# Schematic.net
KiCad netlist of a schematic drawn in EAGLE
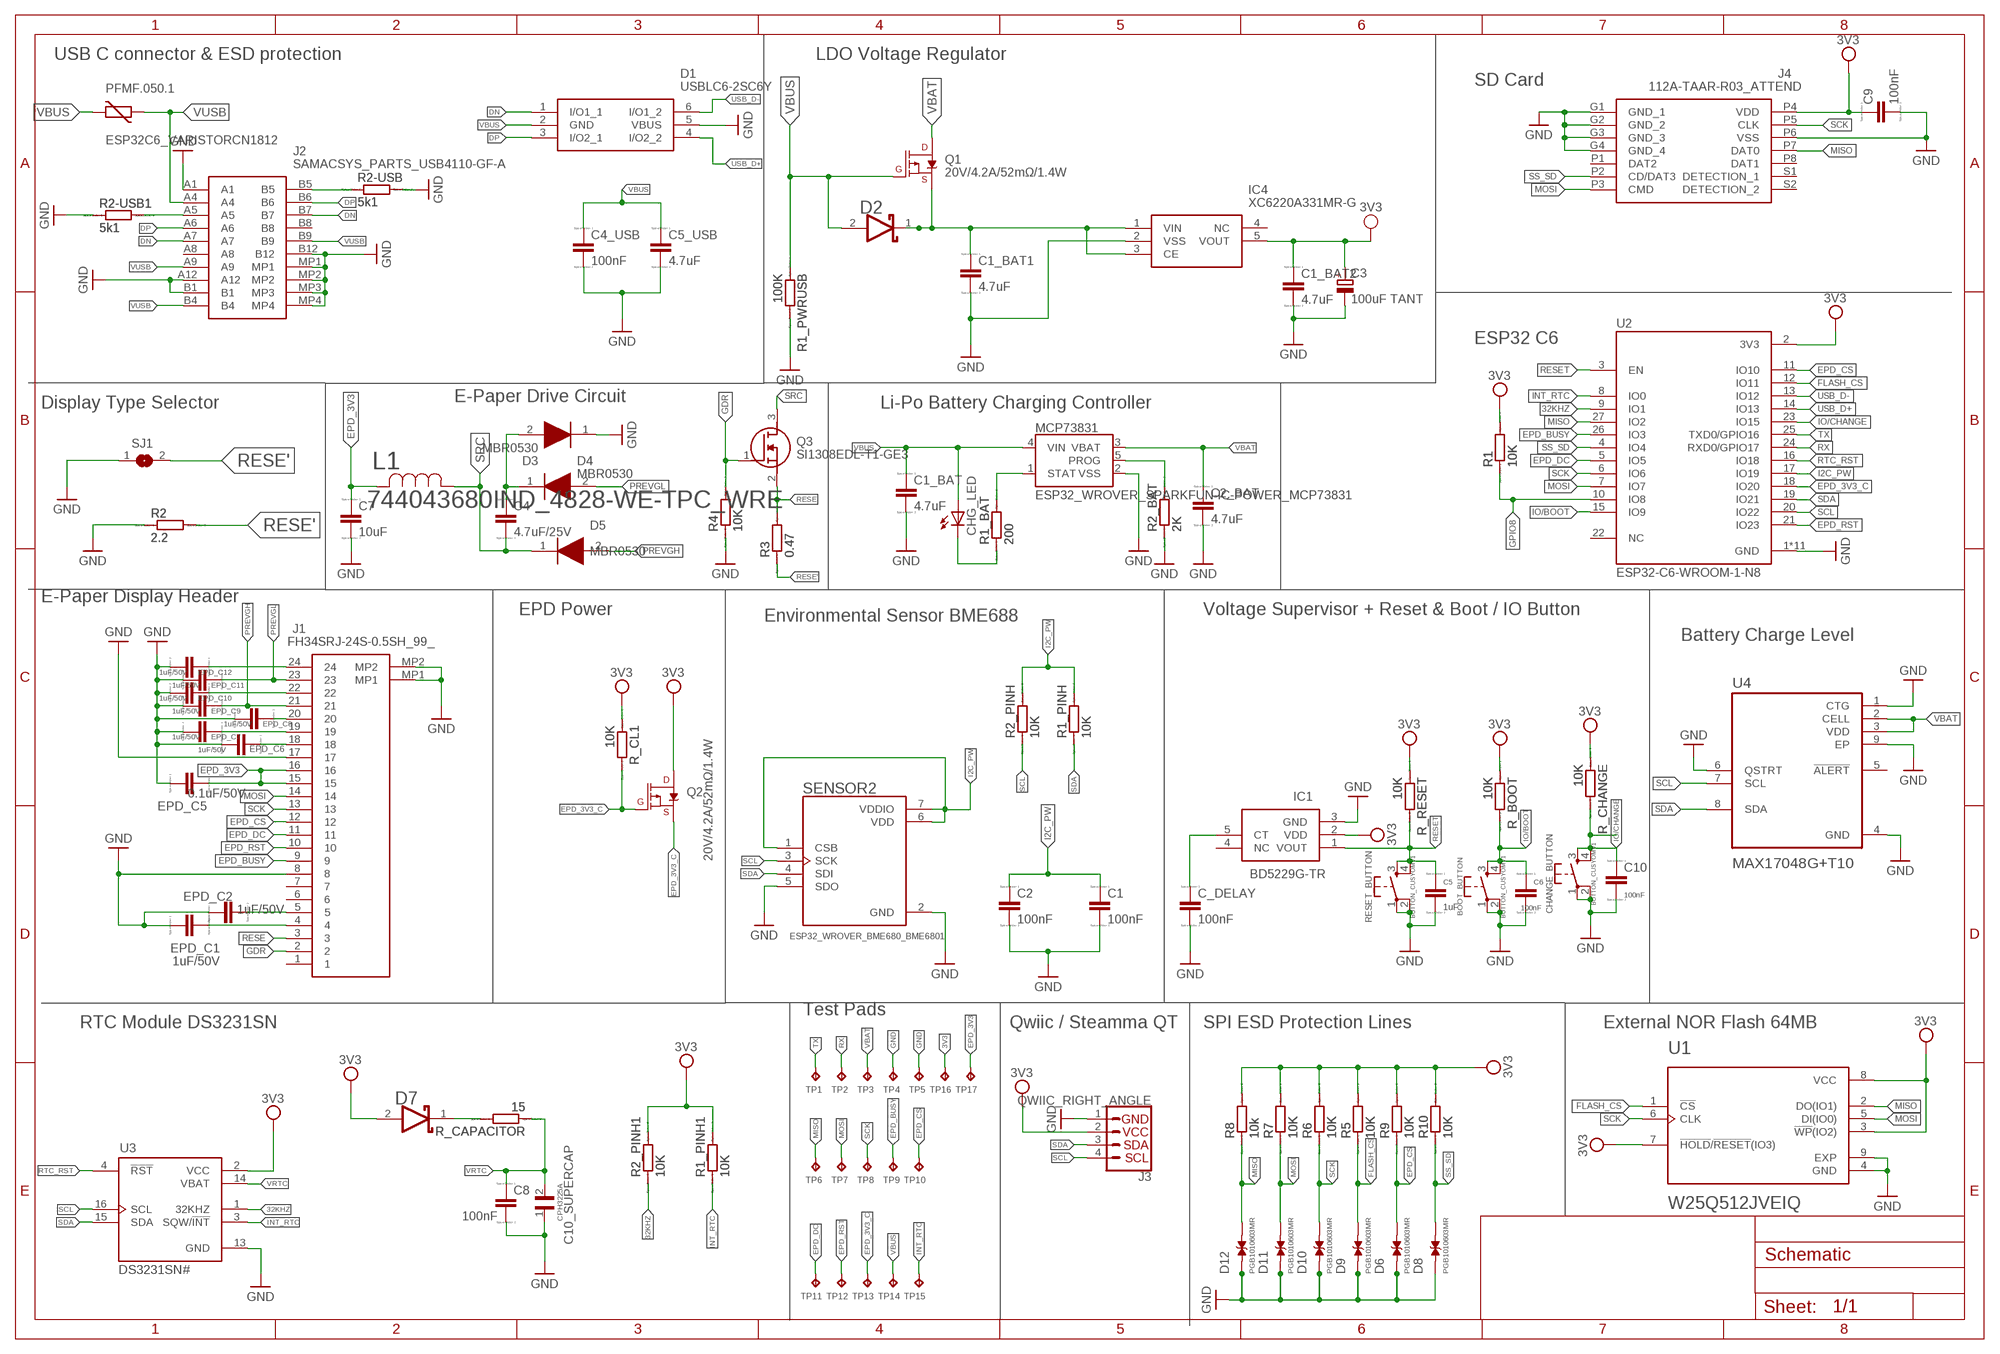
[diagram p0: schematic, sheet 1]

(export (version "E")
  (design (tool "Eeschema 10.0.6"))
  (components
    (comp (ref "BOOT_BUTTON")
      (value "BUTTON_CUSYOMV1")
      (footprint "eagle-import:MYBUTTON")
      (libsource (lib "eagle-import") (part "BUTTON_CUSYOMV1"))
    )
    (comp (ref "C1")
      (value "100nF")
      (footprint "eagle-import:ESP32_WROVER_EAGLE-LTSPICE_C0402")
      (libsource (lib "eagle-import") (part "ESP32_WROVER_EAGLE-LTSPICE_CC0402"))
    )
    (comp (ref "C1_BAT")
      (value "4.7uF")
      (footprint "eagle-import:ESP32_WROVER_EAGLE-LTSPICE_C0402")
      (libsource (lib "eagle-import") (part "ESP32_WROVER_EAGLE-LTSPICE_CC0402"))
    )
    (comp (ref "C1_BAT1")
      (value "4.7uF")
      (footprint "eagle-import:ESP32_WROVER_EAGLE-LTSPICE_C0402")
      (libsource (lib "eagle-import") (part "ESP32_WROVER_EAGLE-LTSPICE_CC0402"))
    )
    (comp (ref "C1_BAT2")
      (value "4.7uF")
      (footprint "eagle-import:ESP32_WROVER_EAGLE-LTSPICE_C0402")
      (libsource (lib "eagle-import") (part "ESP32_WROVER_EAGLE-LTSPICE_CC0402"))
    )
    (comp (ref "C2")
      (value "100nF")
      (footprint "eagle-import:ESP32_WROVER_EAGLE-LTSPICE_C0402")
      (libsource (lib "eagle-import") (part "ESP32_WROVER_EAGLE-LTSPICE_CC0402"))
    )
    (comp (ref "C2_BAT")
      (value "4.7uF")
      (footprint "eagle-import:ESP32_WROVER_EAGLE-LTSPICE_C0402")
      (libsource (lib "eagle-import") (part "ESP32_WROVER_EAGLE-LTSPICE_CC0402"))
    )
    (comp (ref "C3")
      (value "100uF TANT")
      (footprint "eagle-import:RCL_CT3528")
      (libsource (lib "eagle-import") (part "RCL_CPOL-EUCT3528"))
    )
    (comp (ref "C4")
      (value "4.7uF/25V")
      (footprint "eagle-import:ESP32_WROVER_EAGLE-LTSPICE_C0402")
      (libsource (lib "eagle-import") (part "ESP32_WROVER_EAGLE-LTSPICE_CC0402"))
    )
    (comp (ref "C4_USB")
      (value "100nF")
      (footprint "eagle-import:ESP32_WROVER_EAGLE-LTSPICE_C0402")
      (libsource (lib "eagle-import") (part "ESP32_WROVER_EAGLE-LTSPICE_CC0402"))
    )
    (comp (ref "C5")
      (value "1uF")
      (footprint "eagle-import:ESP32_WROVER_EAGLE-LTSPICE_C0402")
      (libsource (lib "eagle-import") (part "ESP32_WROVER_EAGLE-LTSPICE_CC0402"))
    )
    (comp (ref "C5_USB")
      (value "4.7uF")
      (footprint "eagle-import:ESP32_WROVER_EAGLE-LTSPICE_C0402")
      (libsource (lib "eagle-import") (part "ESP32_WROVER_EAGLE-LTSPICE_CC0402"))
    )
    (comp (ref "C6")
      (value "100nF")
      (footprint "eagle-import:ESP32_WROVER_EAGLE-LTSPICE_C0402")
      (libsource (lib "eagle-import") (part "ESP32_WROVER_EAGLE-LTSPICE_CC0402"))
    )
    (comp (ref "C7")
      (value "10uF")
      (footprint "eagle-import:ESP32_WROVER_EAGLE-LTSPICE_C0402")
      (libsource (lib "eagle-import") (part "ESP32_WROVER_EAGLE-LTSPICE_CC0402"))
    )
    (comp (ref "C8")
      (value "100nF")
      (footprint "eagle-import:ESP32_WROVER_EAGLE-LTSPICE_C0402")
      (libsource (lib "eagle-import") (part "ESP32_WROVER_EAGLE-LTSPICE_CC0402"))
    )
    (comp (ref "C9")
      (value "100nF")
      (footprint "eagle-import:ESP32_WROVER_EAGLE-LTSPICE_C0402")
      (libsource (lib "eagle-import") (part "ESP32_WROVER_EAGLE-LTSPICE_CC0402"))
    )
    (comp (ref "C10")
      (value "100nF")
      (footprint "eagle-import:ESP32_WROVER_EAGLE-LTSPICE_C0402")
      (libsource (lib "eagle-import") (part "ESP32_WROVER_EAGLE-LTSPICE_CC0402"))
    )
    (comp (ref "C10_SUPERCAP")
      (value "CPH3225A")
      (footprint "eagle-import:CAPCP3225X100N")
      (fields (field (name "MF") "Seiko Instruments"))
      (libsource (lib "eagle-import") (part "CPH3225A"))
    )
    (comp (ref "CHANGE_BUTTON")
      (value "BUTTON_CUSYOMV1")
      (footprint "eagle-import:MYBUTTON")
      (libsource (lib "eagle-import") (part "BUTTON_CUSYOMV1"))
    )
    (comp (ref "CHG_LED")
      (value "ADAFRUIT_LEDCHIP-LED0603")
      (footprint "eagle-import:ADAFRUIT_CHIP-LED0603")
      (libsource (lib "eagle-import") (part "ADAFRUIT_LEDCHIP-LED0603"))
    )
    (comp (ref "C_DELAY")
      (value "100nF")
      (footprint "eagle-import:ESP32_WROVER_EAGLE-LTSPICE_C0402")
      (libsource (lib "eagle-import") (part "ESP32_WROVER_EAGLE-LTSPICE_CC0402"))
    )
    (comp (ref "D1")
      (value "USBLC6-2SC6Y")
      (footprint "eagle-import:SOT95P280X145-6N")
      (fields (field (name "MF") "STMicroelectronics"))
      (libsource (lib "eagle-import") (part "USBLC6-2SC6Y"))
    )
    (comp (ref "D2")
      (value "ESP32_WROVER_AVX---SD0805S020S1R0_AVX_SD0805S020S1R0_0_0AVX_SD0805S020S1R0_0_0")
      (footprint "eagle-import:ESP32_WROVER_AVX---SD0805S020S1R0_AVX_SD0805S020S1R0_0")
      (fields
        (field (name "DIGIKEY_PART_NUMBER") "478-7800-1-ND")
        (field (name "MF") "AVX")
        (field (name "MOUSER_PART_NUMBER") "581-SD0805S020S1R0")
      )
      (libsource (lib "eagle-import") (part "ESP32_WROVER_AVX---SD0805S020S1R0_AVX_SD0805S020S1R0_0_0AVX_SD0805S020S1R0_0_0"))
    )
    (comp (ref "D3")
      (value "MBR0530")
      (footprint "eagle-import:SOD3716X135N")
      (fields (field (name "MF") "ON Semiconductor"))
      (libsource (lib "eagle-import") (part "MBR0530"))
    )
    (comp (ref "D4")
      (value "MBR0530")
      (footprint "eagle-import:SOD3716X135N")
      (fields (field (name "MF") "ON Semiconductor"))
      (libsource (lib "eagle-import") (part "MBR0530"))
    )
    (comp (ref "D5")
      (value "MBR0530")
      (footprint "eagle-import:SOD3716X135N")
      (fields (field (name "MF") "ON Semiconductor"))
      (libsource (lib "eagle-import") (part "MBR0530"))
    )
    (comp (ref "D6")
      (value "PGB1010603MR")
      (footprint "eagle-import:DIOC1608X36N")
      (fields (field (name "MF") "Littelfuse Inc."))
      (libsource (lib "eagle-import") (part "PGB1010603MR"))
    )
    (comp (ref "D7")
      (value "ESP32_WROVER_AVX---SD0805S020S1R0_AVX_SD0805S020S1R0_0_0AVX_SD0805S020S1R0_0_0")
      (footprint "eagle-import:ESP32_WROVER_AVX---SD0805S020S1R0_AVX_SD0805S020S1R0_0")
      (fields
        (field (name "DIGIKEY_PART_NUMBER") "478-7800-1-ND")
        (field (name "MF") "AVX")
        (field (name "MOUSER_PART_NUMBER") "581-SD0805S020S1R0")
      )
      (libsource (lib "eagle-import") (part "ESP32_WROVER_AVX---SD0805S020S1R0_AVX_SD0805S020S1R0_0_0AVX_SD0805S020S1R0_0_0"))
    )
    (comp (ref "D8")
      (value "PGB1010603MR")
      (footprint "eagle-import:DIOC1608X36N")
      (fields (field (name "MF") "Littelfuse Inc."))
      (libsource (lib "eagle-import") (part "PGB1010603MR"))
    )
    (comp (ref "D9")
      (value "PGB1010603MR")
      (footprint "eagle-import:DIOC1608X36N")
      (fields (field (name "MF") "Littelfuse Inc."))
      (libsource (lib "eagle-import") (part "PGB1010603MR"))
    )
    (comp (ref "D10")
      (value "PGB1010603MR")
      (footprint "eagle-import:DIOC1608X36N")
      (fields (field (name "MF") "Littelfuse Inc."))
      (libsource (lib "eagle-import") (part "PGB1010603MR"))
    )
    (comp (ref "D11")
      (value "PGB1010603MR")
      (footprint "eagle-import:DIOC1608X36N")
      (fields (field (name "MF") "Littelfuse Inc."))
      (libsource (lib "eagle-import") (part "PGB1010603MR"))
    )
    (comp (ref "D12")
      (value "PGB1010603MR")
      (footprint "eagle-import:DIOC1608X36N")
      (fields (field (name "MF") "Littelfuse Inc."))
      (libsource (lib "eagle-import") (part "PGB1010603MR"))
    )
    (comp (ref "EPD_C1")
      (value "1uF/50V")
      (footprint "eagle-import:ESP32_WROVER_EAGLE-LTSPICE_C0402")
      (libsource (lib "eagle-import") (part "ESP32_WROVER_EAGLE-LTSPICE_CC0402"))
    )
    (comp (ref "EPD_C2")
      (value "1uF/50V")
      (footprint "eagle-import:ESP32_WROVER_EAGLE-LTSPICE_C0402")
      (libsource (lib "eagle-import") (part "ESP32_WROVER_EAGLE-LTSPICE_CC0402"))
    )
    (comp (ref "EPD_C5")
      (value "0.1uF/50V")
      (footprint "eagle-import:ESP32_WROVER_EAGLE-LTSPICE_C0402")
      (libsource (lib "eagle-import") (part "ESP32_WROVER_EAGLE-LTSPICE_CC0402"))
    )
    (comp (ref "EPD_C6")
      (value "1uF/50V")
      (footprint "eagle-import:ESP32_WROVER_EAGLE-LTSPICE_C0402")
      (libsource (lib "eagle-import") (part "ESP32_WROVER_EAGLE-LTSPICE_CC0402"))
    )
    (comp (ref "EPD_C7")
      (value "1uF/50V")
      (footprint "eagle-import:ESP32_WROVER_EAGLE-LTSPICE_C0402")
      (libsource (lib "eagle-import") (part "ESP32_WROVER_EAGLE-LTSPICE_CC0402"))
    )
    (comp (ref "EPD_C8")
      (value "1uF/50V")
      (footprint "eagle-import:ESP32_WROVER_EAGLE-LTSPICE_C0402")
      (libsource (lib "eagle-import") (part "ESP32_WROVER_EAGLE-LTSPICE_CC0402"))
    )
    (comp (ref "EPD_C9")
      (value "1uF/50V")
      (footprint "eagle-import:ESP32_WROVER_EAGLE-LTSPICE_C0402")
      (libsource (lib "eagle-import") (part "ESP32_WROVER_EAGLE-LTSPICE_CC0402"))
    )
    (comp (ref "EPD_C10")
      (value "1uF/50V")
      (footprint "eagle-import:ESP32_WROVER_EAGLE-LTSPICE_C0402")
      (libsource (lib "eagle-import") (part "ESP32_WROVER_EAGLE-LTSPICE_CC0402"))
    )
    (comp (ref "EPD_C11")
      (value "1uF/50V")
      (footprint "eagle-import:ESP32_WROVER_EAGLE-LTSPICE_C0402")
      (libsource (lib "eagle-import") (part "ESP32_WROVER_EAGLE-LTSPICE_CC0402"))
    )
    (comp (ref "EPD_C12")
      (value "1uF/50V")
      (footprint "eagle-import:ESP32_WROVER_EAGLE-LTSPICE_C0402")
      (libsource (lib "eagle-import") (part "ESP32_WROVER_EAGLE-LTSPICE_CC0402"))
    )
    (comp (ref "IC1")
      (value "BD5229G-TR")
      (footprint "eagle-import:SOT95P280X125-5N")
      (fields (field (name "MOUSER_PART_NUMBER") "755-BD5229G-TR"))
      (libsource (lib "eagle-import") (part "BD5229G-TR"))
    )
    (comp (ref "IC4")
      (value "XC6220A331MR-G")
      (footprint "eagle-import:SOT95P280X120-5N")
      (fields (field (name "MOUSER_PART_NUMBER") "865-XC6220A331MR-G"))
      (libsource (lib "eagle-import") (part "XC6220A331MR-G"))
    )
    (comp (ref "J1")
      (value "FH34SRJ-24S-0.5SH_99_")
      (footprint "eagle-import:FH34SRJ24S05SH99")
      (fields
        (field (name "MANUFACTURER_PART_NUMBER") "FH34SRJ-24S-0.5SH(99)")
        (field (name "MOUSER_PART_NUMBER") "798-FH34SRJ24S05SH99")
      )
      (libsource (lib "eagle-import") (part "FH34SRJ-24S-0.5SH_99_"))
    )
    (comp (ref "J2")
      (value "SAMACSYS_PARTS_USB4110-GF-A")
      (footprint "eagle-import:SAMACSYS_PARTS_USB4110GFA")
      (fields
        (field (name "MANUFACTURER_PART_NUMBER") "USB4110-GF-A")
        (field (name "MOUSER_PART_NUMBER") "640-USB4110-GF-A")
      )
      (libsource (lib "eagle-import") (part "SAMACSYS_PARTS_USB4110-GF-A"))
    )
    (comp (ref "J3")
      (value "QWIIC_RIGHT_ANGLE")
      (footprint "eagle-import:JST04_1MM_RA")
      (libsource (lib "eagle-import") (part "QWIIC_CONNECTORJS-1MM"))
    )
    (comp (ref "J4")
      (value "112A-TAAR-R03_ATTEND")
      (footprint "eagle-import:112ATAARR03ATTEND")
      (fields (field (name "MANUFACTURER_PART_NUMBER") "112A-TAAR-R03 ATTEND"))
      (libsource (lib "eagle-import") (part "112A-TAAR-R03_ATTEND"))
    )
    (comp (ref "L1")
      (value "744043680IND_4828-WE-TPC_WRE")
      (footprint "eagle-import:IND_4828-WE-TPC_WRE")
      (fields
        (field (name "MANUFACTURER_PART_NUMBER") "744043680")
        (field (name "COPYRIGHT") "Copyright (C) 2024 Ultra Librarian. All rights reserved.")
      )
      (libsource (lib "eagle-import") (part "744043680IND_4828-WE-TPC_WRE"))
    )
    (comp (ref "MCP73831")
      (value "ESP32_WROVER_SPARKFUN-IC-POWER_MCP73831")
      (footprint "eagle-import:ESP32_WROVER_SPARKFUN-IC-POWER_SOT23-5")
      (libsource (lib "eagle-import") (part "ESP32_WROVER_SPARKFUN-IC-POWER_MCP73831"))
    )
    (comp (ref "PFMF.050.1")
      (value "ESP32C6_VARISTORCN1812")
      (footprint "eagle-import:ESP32C6_VARISTOR_CT_CN1812")
      (libsource (lib "eagle-import") (part "ESP32C6_VARISTORCN1812"))
    )
    (comp (ref "Q1")
      (value "20V/4.2A/52mΩ/1.4W")
      (footprint "eagle-import:ESP32_WROVER_SPARKFUN-DISCRETESEMI_SOT23-3")
      (libsource (lib "eagle-import") (part "ESP32_WROVER_SPARKFUN-DISCRETESEMI_MOSFET_PCH-DMG2305UX-7"))
    )
    (comp (ref "Q2")
      (value "20V/4.2A/52mΩ/1.4W")
      (footprint "eagle-import:ESP32_WROVER_SPARKFUN-DISCRETESEMI_SOT23-3")
      (libsource (lib "eagle-import") (part "ESP32_WROVER_SPARKFUN-DISCRETESEMI_MOSFET_PCH-DMG2305UX-7"))
    )
    (comp (ref "Q3")
      (value "SI1308EDL-T1-GE3")
      (footprint "eagle-import:SOT65P210X110-3N")
      (fields (field (name "MF") "Vishay Siliconix"))
      (libsource (lib "eagle-import") (part "SI1308EDL-T1-GE3"))
    )
    (comp (ref "R1")
      (value "10K")
      (footprint "eagle-import:ESP32_WROVER_EAGLE-LTSPICE_R0402")
      (libsource (lib "eagle-import") (part "ESP32_WROVER_EAGLE-LTSPICE_RR0402"))
    )
    (comp (ref "R1_BAT")
      (value "200")
      (footprint "eagle-import:ESP32_WROVER_EAGLE-LTSPICE_R0402")
      (libsource (lib "eagle-import") (part "ESP32_WROVER_EAGLE-LTSPICE_RR0402"))
    )
    (comp (ref "R1_PINH")
      (value "10K")
      (footprint "eagle-import:ESP32_WROVER_EAGLE-LTSPICE_R0402")
      (libsource (lib "eagle-import") (part "ESP32_WROVER_EAGLE-LTSPICE_RR0402"))
    )
    (comp (ref "R1_PINH1")
      (value "10K")
      (footprint "eagle-import:ESP32_WROVER_EAGLE-LTSPICE_R0402")
      (libsource (lib "eagle-import") (part "ESP32_WROVER_EAGLE-LTSPICE_RR0402"))
    )
    (comp (ref "R1_PWRUSB")
      (value "100K")
      (footprint "eagle-import:ESP32_WROVER_EAGLE-LTSPICE_R0402")
      (libsource (lib "eagle-import") (part "ESP32_WROVER_EAGLE-LTSPICE_RR0402"))
    )
    (comp (ref "R2")
      (value "2.2")
      (footprint "eagle-import:ESP32_WROVER_EAGLE-LTSPICE_R0402")
      (libsource (lib "eagle-import") (part "ESP32_WROVER_EAGLE-LTSPICE_RR0402"))
    )
    (comp (ref "R2-USB")
      (value "5k1")
      (footprint "eagle-import:ESP32_WROVER_EAGLE-LTSPICE_R0402")
      (libsource (lib "eagle-import") (part "ESP32_WROVER_EAGLE-LTSPICE_RR0402"))
    )
    (comp (ref "R2-USB1")
      (value "5k1")
      (footprint "eagle-import:ESP32_WROVER_EAGLE-LTSPICE_R0402")
      (libsource (lib "eagle-import") (part "ESP32_WROVER_EAGLE-LTSPICE_RR0402"))
    )
    (comp (ref "R2_BAT")
      (value "2K")
      (footprint "eagle-import:ESP32_WROVER_EAGLE-LTSPICE_R0402")
      (libsource (lib "eagle-import") (part "ESP32_WROVER_EAGLE-LTSPICE_RR0402"))
    )
    (comp (ref "R2_PINH")
      (value "10K")
      (footprint "eagle-import:ESP32_WROVER_EAGLE-LTSPICE_R0402")
      (libsource (lib "eagle-import") (part "ESP32_WROVER_EAGLE-LTSPICE_RR0402"))
    )
    (comp (ref "R2_PINH1")
      (value "10K")
      (footprint "eagle-import:ESP32_WROVER_EAGLE-LTSPICE_R0402")
      (libsource (lib "eagle-import") (part "ESP32_WROVER_EAGLE-LTSPICE_RR0402"))
    )
    (comp (ref "R3")
      (value "0.47")
      (footprint "eagle-import:ESP32_WROVER_EAGLE-LTSPICE_R0402")
      (libsource (lib "eagle-import") (part "ESP32_WROVER_EAGLE-LTSPICE_RR0402"))
    )
    (comp (ref "R4")
      (value "10K")
      (footprint "eagle-import:ESP32_WROVER_EAGLE-LTSPICE_R0402")
      (libsource (lib "eagle-import") (part "ESP32_WROVER_EAGLE-LTSPICE_RR0402"))
    )
    (comp (ref "R5")
      (value "10K")
      (footprint "eagle-import:ESP32_WROVER_EAGLE-LTSPICE_R0402")
      (libsource (lib "eagle-import") (part "ESP32_WROVER_EAGLE-LTSPICE_RR0402"))
    )
    (comp (ref "R6")
      (value "10K")
      (footprint "eagle-import:ESP32_WROVER_EAGLE-LTSPICE_R0402")
      (libsource (lib "eagle-import") (part "ESP32_WROVER_EAGLE-LTSPICE_RR0402"))
    )
    (comp (ref "R7")
      (value "10K")
      (footprint "eagle-import:ESP32_WROVER_EAGLE-LTSPICE_R0402")
      (libsource (lib "eagle-import") (part "ESP32_WROVER_EAGLE-LTSPICE_RR0402"))
    )
    (comp (ref "R8")
      (value "10k")
      (footprint "eagle-import:ESP32_WROVER_EAGLE-LTSPICE_R0402")
      (libsource (lib "eagle-import") (part "ESP32_WROVER_EAGLE-LTSPICE_RR0402"))
    )
    (comp (ref "R9")
      (value "10K")
      (footprint "eagle-import:ESP32_WROVER_EAGLE-LTSPICE_R0402")
      (libsource (lib "eagle-import") (part "ESP32_WROVER_EAGLE-LTSPICE_RR0402"))
    )
    (comp (ref "R10")
      (value "10K")
      (footprint "eagle-import:ESP32_WROVER_EAGLE-LTSPICE_R0402")
      (libsource (lib "eagle-import") (part "ESP32_WROVER_EAGLE-LTSPICE_RR0402"))
    )
    (comp (ref "RESET_BUTTON")
      (value "BUTTON_CUSYOMV1")
      (footprint "eagle-import:MYBUTTON")
      (libsource (lib "eagle-import") (part "BUTTON_CUSYOMV1"))
    )
    (comp (ref "R_BOOT")
      (value "10K")
      (footprint "eagle-import:ESP32_WROVER_EAGLE-LTSPICE_R0402")
      (libsource (lib "eagle-import") (part "ESP32_WROVER_EAGLE-LTSPICE_RR0402"))
    )
    (comp (ref "R_CAPACITOR")
      (value "15")
      (footprint "eagle-import:ESP32_WROVER_EAGLE-LTSPICE_R0402")
      (libsource (lib "eagle-import") (part "ESP32_WROVER_EAGLE-LTSPICE_RR0402"))
    )
    (comp (ref "R_CHANGE")
      (value "10K")
      (footprint "eagle-import:ESP32_WROVER_EAGLE-LTSPICE_R0402")
      (libsource (lib "eagle-import") (part "ESP32_WROVER_EAGLE-LTSPICE_RR0402"))
    )
    (comp (ref "R_CL1")
      (value "10K")
      (footprint "eagle-import:ESP32_WROVER_EAGLE-LTSPICE_R0402")
      (libsource (lib "eagle-import") (part "ESP32_WROVER_EAGLE-LTSPICE_RR0402"))
    )
    (comp (ref "R_RESET")
      (value "10K")
      (footprint "eagle-import:ESP32_WROVER_EAGLE-LTSPICE_R0402")
      (libsource (lib "eagle-import") (part "ESP32_WROVER_EAGLE-LTSPICE_RR0402"))
    )
    (comp (ref "SENSOR2")
      (value "ESP32_WROVER_BME680_BME6801")
      (footprint "eagle-import:ESP32_WROVER_BME680_PSON80P300X300X100-8N")
      (libsource (lib "eagle-import") (part "ESP32_WROVER_BME680_BME6801"))
    )
    (comp (ref "SJ1") (value "SJ") (footprint "eagle-import:SJ") (libsource (lib "eagle-import") (part "SJ")))
    (comp (ref "TP1")
      (value "TPTP20R")
      (footprint "eagle-import:TP20R")
      (libsource (lib "eagle-import") (part "TPTP20R"))
    )
    (comp (ref "TP2")
      (value "TPTP20R")
      (footprint "eagle-import:TP20R")
      (libsource (lib "eagle-import") (part "TPTP20R"))
    )
    (comp (ref "TP3")
      (value "TPTP20R")
      (footprint "eagle-import:TP20R")
      (libsource (lib "eagle-import") (part "TPTP20R"))
    )
    (comp (ref "TP4")
      (value "TPTP20R")
      (footprint "eagle-import:TP20R")
      (libsource (lib "eagle-import") (part "TPTP20R"))
    )
    (comp (ref "TP5")
      (value "TPTP20R")
      (footprint "eagle-import:TP20R")
      (libsource (lib "eagle-import") (part "TPTP20R"))
    )
    (comp (ref "TP6")
      (value "TPTP20R")
      (footprint "eagle-import:TP20R")
      (libsource (lib "eagle-import") (part "TPTP20R"))
    )
    (comp (ref "TP7")
      (value "TPTP20R")
      (footprint "eagle-import:TP20R")
      (libsource (lib "eagle-import") (part "TPTP20R"))
    )
    (comp (ref "TP8")
      (value "TPTP20R")
      (footprint "eagle-import:TP20R")
      (libsource (lib "eagle-import") (part "TPTP20R"))
    )
    (comp (ref "TP9")
      (value "TPTP20R")
      (footprint "eagle-import:TP20R")
      (libsource (lib "eagle-import") (part "TPTP20R"))
    )
    (comp (ref "TP10")
      (value "TPTP20R")
      (footprint "eagle-import:TP20R")
      (libsource (lib "eagle-import") (part "TPTP20R"))
    )
    (comp (ref "TP11")
      (value "TPTP20R")
      (footprint "eagle-import:TP20R")
      (libsource (lib "eagle-import") (part "TPTP20R"))
    )
    (comp (ref "TP12")
      (value "TPTP20R")
      (footprint "eagle-import:TP20R")
      (libsource (lib "eagle-import") (part "TPTP20R"))
    )
    (comp (ref "TP13")
      (value "TPTP20R")
      (footprint "eagle-import:TP20R")
      (libsource (lib "eagle-import") (part "TPTP20R"))
    )
    (comp (ref "TP14")
      (value "TPTP20R")
      (footprint "eagle-import:TP20R")
      (libsource (lib "eagle-import") (part "TPTP20R"))
    )
    (comp (ref "TP15")
      (value "TPTP20R")
      (footprint "eagle-import:TP20R")
      (libsource (lib "eagle-import") (part "TPTP20R"))
    )
    (comp (ref "TP16")
      (value "TPTP20R")
      (footprint "eagle-import:TP20R")
      (libsource (lib "eagle-import") (part "TPTP20R"))
    )
    (comp (ref "TP17")
      (value "TPTP20R")
      (footprint "eagle-import:TP20R")
      (libsource (lib "eagle-import") (part "TPTP20R"))
    )
    (comp (ref "U1")
      (value "W25Q512JVEIQ")
      (footprint "eagle-import:SON127P600X800X80-9N")
      (fields (field (name "MF") "Winbond Electronics"))
      (libsource (lib "eagle-import") (part "W25Q512JVEIQ"))
    )
    (comp (ref "U2")
      (value "ESP32-C6-WROOM-1-N8")
      (footprint "eagle-import:XCVR_ESP32-C6-WROOM-1-N8")
      (fields (field (name "MF") "Espressif Systems"))
      (libsource (lib "eagle-import") (part "ESP32-C6-WROOM-1-N8"))
    )
    (comp (ref "U3")
      (value "DS3231SN#")
      (footprint "eagle-import:SOIC127P1032X265-16N")
      (fields (field (name "MF") "Analog Devices"))
      (libsource (lib "eagle-import") (part "DS3231SN#"))
    )
    (comp (ref "U4")
      (value "MAX17048G+T10")
      (footprint "eagle-import:SON50P200X200X80-9N")
      (fields (field (name "MF") "Analog Devices"))
      (libsource (lib "eagle-import") (part "MAX17048G+T10"))
    )
  )
  (nets
    (net (code "1") (name "3V3") (class "Default")
      (node (ref "C1_BAT2") (pin "1") (pinfunction "1_1") (pintype "passive"))
      (node (ref "C3") (pin "+") (pinfunction "+_+") (pintype "passive"))
      (node (ref "C9") (pin "1") (pinfunction "1_1") (pintype "passive"))
      (node (ref "D7") (pin "2") (pinfunction "ANODE_2") (pintype "bidirectional"))
      (node (ref "IC1") (pin "2") (pinfunction "VDD_2") (pintype "bidirectional"))
      (node (ref "IC4") (pin "5") (pinfunction "VOUT_5") (pintype "bidirectional"))
      (node (ref "J3") (pin "2") (pinfunction "2_2") (pintype "power_in"))
      (node (ref "J4") (pin "P4") (pinfunction "VDD_P4") (pintype "bidirectional"))
      (node (ref "Q2") (pin "3") (pinfunction "D_3") (pintype "bidirectional"))
      (node (ref "R1") (pin "2") (pinfunction "2_2") (pintype "passive"))
      (node (ref "R10") (pin "2") (pinfunction "2_2") (pintype "passive"))
      (node (ref "R1_PINH1") (pin "2") (pinfunction "2_2") (pintype "passive"))
      (node (ref "R2_PINH1") (pin "2") (pinfunction "2_2") (pintype "passive"))
      (node (ref "R5") (pin "2") (pinfunction "2_2") (pintype "passive"))
      (node (ref "R6") (pin "2") (pinfunction "2_2") (pintype "passive"))
      (node (ref "R7") (pin "2") (pinfunction "2_2") (pintype "passive"))
      (node (ref "R8") (pin "2") (pinfunction "2_2") (pintype "passive"))
      (node (ref "R9") (pin "2") (pinfunction "2_2") (pintype "passive"))
      (node (ref "R_BOOT") (pin "1") (pinfunction "1_1") (pintype "passive"))
      (node (ref "R_CHANGE") (pin "1") (pinfunction "1_1") (pintype "passive"))
      (node (ref "R_CL1") (pin "1") (pinfunction "1_1") (pintype "passive"))
      (node (ref "R_RESET") (pin "1") (pinfunction "1_1") (pintype "passive"))
      (node (ref "TP16") (pin "TP") (pinfunction "TP_TP") (pintype "input"))
      (node (ref "U1") (pin "3") (pinfunction "~{WP}(IO2)_3") (pintype "bidirectional"))
      (node (ref "U1") (pin "7") (pinfunction "~{HOLD}/~{RESET}(IO3)_7") (pintype "bidirectional"))
      (node (ref "U1") (pin "8") (pinfunction "VCC_8") (pintype "power_in"))
      (node (ref "U2") (pin "2") (pinfunction "3V3_2") (pintype "power_in"))
      (node (ref "U3") (pin "2") (pinfunction "VCC_2") (pintype "power_in"))
    )
    (net (code "2") (name "32KHZ") (class "Default")
      (node (ref "R2_PINH1") (pin "1") (pinfunction "1_1") (pintype "passive"))
      (node (ref "U2") (pin "9") (pinfunction "IO1_9") (pintype "bidirectional"))
      (node (ref "U3") (pin "1") (pinfunction "32KHZ_1") (pintype "output"))
    )
    (net (code "3") (name "DN") (class "Default")
      (node (ref "D1") (pin "1") (pinfunction "I/O1_1_1") (pintype "bidirectional"))
      (node (ref "J2") (pin "A7") (pinfunction "A7_A7") (pintype "bidirectional"))
      (node (ref "J2") (pin "B7") (pinfunction "B7_B7") (pintype "bidirectional"))
    )
    (net (code "4") (name "DP") (class "Default")
      (node (ref "D1") (pin "3") (pinfunction "I/O2_1_3") (pintype "bidirectional"))
      (node (ref "J2") (pin "A6") (pinfunction "A6_A6") (pintype "bidirectional"))
      (node (ref "J2") (pin "B6") (pinfunction "B6_B6") (pintype "bidirectional"))
    )
    (net (code "5") (name "EPD_3V3") (class "Default")
      (node (ref "C7") (pin "1") (pinfunction "1_1") (pintype "passive"))
      (node (ref "EPD_C5") (pin "2") (pinfunction "2_2") (pintype "passive"))
      (node (ref "J1") (pin "15") (pinfunction "15_15") (pintype "bidirectional"))
      (node (ref "J1") (pin "16") (pinfunction "16_16") (pintype "bidirectional"))
      (node (ref "L1") (pin "2") (pinfunction "2_2") (pintype "passive"))
      (node (ref "TP17") (pin "TP") (pinfunction "TP_TP") (pintype "input"))
    )
    (net (code "6") (name "EPD_3V3_C") (class "Default")
      (node (ref "Q2") (pin "1") (pinfunction "G_1") (pintype "bidirectional"))
      (node (ref "Q2") (pin "2") (pinfunction "S_2") (pintype "bidirectional"))
      (node (ref "R_CL1") (pin "2") (pinfunction "2_2") (pintype "passive"))
      (node (ref "TP13") (pin "TP") (pinfunction "TP_TP") (pintype "input"))
      (node (ref "U2") (pin "18") (pinfunction "IO20_18") (pintype "bidirectional"))
    )
    (net (code "7") (name "EPD_BUSY") (class "Default")
      (node (ref "J1") (pin "9") (pinfunction "9_9") (pintype "bidirectional"))
      (node (ref "TP9") (pin "TP") (pinfunction "TP_TP") (pintype "input"))
      (node (ref "U2") (pin "26") (pinfunction "IO3_26") (pintype "bidirectional"))
    )
    (net (code "8") (name "EPD_CS") (class "Default")
      (node (ref "D6") (pin "2") (pinfunction "2_2") (pintype "passive"))
      (node (ref "J1") (pin "12") (pinfunction "12_12") (pintype "bidirectional"))
      (node (ref "R9") (pin "1") (pinfunction "1_1") (pintype "passive"))
      (node (ref "TP10") (pin "TP") (pinfunction "TP_TP") (pintype "input"))
      (node (ref "U2") (pin "11") (pinfunction "IO10_11") (pintype "bidirectional"))
    )
    (net (code "9") (name "EPD_DC") (class "Default")
      (node (ref "J1") (pin "11") (pinfunction "11_11") (pintype "bidirectional"))
      (node (ref "TP11") (pin "TP") (pinfunction "TP_TP") (pintype "input"))
      (node (ref "U2") (pin "5") (pinfunction "IO5_5") (pintype "bidirectional"))
    )
    (net (code "10") (name "EPD_RST") (class "Default")
      (node (ref "J1") (pin "10") (pinfunction "10_10") (pintype "bidirectional"))
      (node (ref "TP12") (pin "TP") (pinfunction "TP_TP") (pintype "input"))
      (node (ref "U2") (pin "21") (pinfunction "IO23_21") (pintype "bidirectional"))
    )
    (net (code "11") (name "FLASH_CS") (class "Default")
      (node (ref "D9") (pin "2") (pinfunction "2_2") (pintype "passive"))
      (node (ref "R5") (pin "1") (pinfunction "1_1") (pintype "passive"))
      (node (ref "U1") (pin "1") (pinfunction "~{CS}_1") (pintype "input"))
      (node (ref "U2") (pin "12") (pinfunction "IO11_12") (pintype "bidirectional"))
    )
    (net (code "12") (name "GDR") (class "Default")
      (node (ref "J1") (pin "2") (pinfunction "2_2") (pintype "bidirectional"))
      (node (ref "Q3") (pin "1") (pinfunction "G_1") (pintype "bidirectional"))
      (node (ref "R4") (pin "2") (pinfunction "2_2") (pintype "passive"))
    )
    (net (code "13") (name "GND") (class "Default")
      (node (ref "BOOT_BUTTON") (pin "1") (pinfunction "1_1") (pintype "passive"))
      (node (ref "BOOT_BUTTON") (pin "2") (pinfunction "2_2") (pintype "passive"))
      (node (ref "C1") (pin "2") (pinfunction "2_2") (pintype "passive"))
      (node (ref "C10") (pin "2") (pinfunction "2_2") (pintype "passive"))
      (node (ref "C10_SUPERCAP") (pin "1") (pinfunction "1_1") (pintype "passive"))
      (node (ref "C1_BAT") (pin "2") (pinfunction "2_2") (pintype "passive"))
      (node (ref "C1_BAT1") (pin "2") (pinfunction "2_2") (pintype "passive"))
      (node (ref "C1_BAT2") (pin "2") (pinfunction "2_2") (pintype "passive"))
      (node (ref "C2") (pin "2") (pinfunction "2_2") (pintype "passive"))
      (node (ref "C2_BAT") (pin "2") (pinfunction "2_2") (pintype "passive"))
      (node (ref "C3") (pin "-") (pinfunction "-_-") (pintype "passive"))
      (node (ref "C4_USB") (pin "2") (pinfunction "2_2") (pintype "passive"))
      (node (ref "C5") (pin "2") (pinfunction "2_2") (pintype "passive"))
      (node (ref "C5_USB") (pin "2") (pinfunction "2_2") (pintype "passive"))
      (node (ref "C6") (pin "2") (pinfunction "2_2") (pintype "passive"))
      (node (ref "C7") (pin "2") (pinfunction "2_2") (pintype "passive"))
      (node (ref "C8") (pin "2") (pinfunction "2_2") (pintype "passive"))
      (node (ref "C9") (pin "2") (pinfunction "2_2") (pintype "passive"))
      (node (ref "CHANGE_BUTTON") (pin "1") (pinfunction "1_1") (pintype "passive"))
      (node (ref "CHANGE_BUTTON") (pin "2") (pinfunction "2_2") (pintype "passive"))
      (node (ref "C_DELAY") (pin "2") (pinfunction "2_2") (pintype "passive"))
      (node (ref "D1") (pin "5") (pinfunction "VBUS_5") (pintype "bidirectional"))
      (node (ref "D10") (pin "1") (pinfunction "1_1") (pintype "passive"))
      (node (ref "D11") (pin "1") (pinfunction "1_1") (pintype "passive"))
      (node (ref "D12") (pin "1") (pinfunction "1_1") (pintype "passive"))
      (node (ref "D3") (pin "1") (pinfunction "K_1") (pintype "bidirectional"))
      (node (ref "D6") (pin "1") (pinfunction "1_1") (pintype "passive"))
      (node (ref "D8") (pin "1") (pinfunction "1_1") (pintype "passive"))
      (node (ref "D9") (pin "1") (pinfunction "1_1") (pintype "passive"))
      (node (ref "EPD_C1") (pin "1") (pinfunction "1_1") (pintype "passive"))
      (node (ref "EPD_C10") (pin "2") (pinfunction "2_2") (pintype "passive"))
      (node (ref "EPD_C11") (pin "2") (pinfunction "2_2") (pintype "passive"))
      (node (ref "EPD_C12") (pin "2") (pinfunction "2_2") (pintype "passive"))
      (node (ref "EPD_C2") (pin "1") (pinfunction "1_1") (pintype "passive"))
      (node (ref "EPD_C5") (pin "1") (pinfunction "1_1") (pintype "passive"))
      (node (ref "EPD_C6") (pin "2") (pinfunction "2_2") (pintype "passive"))
      (node (ref "EPD_C7") (pin "2") (pinfunction "2_2") (pintype "passive"))
      (node (ref "EPD_C8") (pin "2") (pinfunction "2_2") (pintype "passive"))
      (node (ref "EPD_C9") (pin "2") (pinfunction "2_2") (pintype "passive"))
      (node (ref "IC1") (pin "3") (pinfunction "GND_3") (pintype "bidirectional"))
      (node (ref "IC4") (pin "2") (pinfunction "VSS_2") (pintype "bidirectional"))
      (node (ref "J1") (pin "17") (pinfunction "17_17") (pintype "bidirectional"))
      (node (ref "J1") (pin "8") (pinfunction "8_8") (pintype "bidirectional"))
      (node (ref "J1") (pin "MP1") (pinfunction "MP1_MP1") (pintype "bidirectional"))
      (node (ref "J1") (pin "MP2") (pinfunction "MP2_MP2") (pintype "bidirectional"))
      (node (ref "J2") (pin "A1") (pinfunction "A1_A1") (pintype "bidirectional"))
      (node (ref "J2") (pin "A12") (pinfunction "A12_A12") (pintype "bidirectional"))
      (node (ref "J2") (pin "B1") (pinfunction "B1_B1") (pintype "bidirectional"))
      (node (ref "J2") (pin "B12") (pinfunction "B12_B12") (pintype "bidirectional"))
      (node (ref "J2") (pin "MP1") (pinfunction "MP1_MP1") (pintype "bidirectional"))
      (node (ref "J2") (pin "MP2") (pinfunction "MP2_MP2") (pintype "bidirectional"))
      (node (ref "J2") (pin "MP3") (pinfunction "MP3_MP3") (pintype "bidirectional"))
      (node (ref "J2") (pin "MP4") (pinfunction "MP4_MP4") (pintype "bidirectional"))
      (node (ref "J3") (pin "1") (pinfunction "1_1") (pintype "power_in"))
      (node (ref "J4") (pin "G1") (pinfunction "GND_1_G1") (pintype "bidirectional"))
      (node (ref "J4") (pin "G2") (pinfunction "GND_2_G2") (pintype "bidirectional"))
      (node (ref "J4") (pin "G3") (pinfunction "GND_3_G3") (pintype "bidirectional"))
      (node (ref "J4") (pin "G4") (pinfunction "GND_4_G4") (pintype "bidirectional"))
      (node (ref "J4") (pin "P6") (pinfunction "VSS_P6") (pintype "bidirectional"))
      (node (ref "MCP73831") (pin "2") (pinfunction "VSS_2") (pintype "power_in"))
      (node (ref "R1_PWRUSB") (pin "2") (pinfunction "2_2") (pintype "passive"))
      (node (ref "R2") (pin "1") (pinfunction "1_1") (pintype "passive"))
      (node (ref "R2-USB") (pin "2") (pinfunction "2_2") (pintype "passive"))
      (node (ref "R2-USB1") (pin "1") (pinfunction "1_1") (pintype "passive"))
      (node (ref "R2_BAT") (pin "1") (pinfunction "1_1") (pintype "passive"))
      (node (ref "R4") (pin "1") (pinfunction "1_1") (pintype "passive"))
      (node (ref "RESET_BUTTON") (pin "1") (pinfunction "1_1") (pintype "passive"))
      (node (ref "RESET_BUTTON") (pin "2") (pinfunction "2_2") (pintype "passive"))
      (node (ref "SENSOR2") (pin "2") (pinfunction "GND_2") (pintype "power_in"))
      (node (ref "SENSOR2") (pin "5") (pinfunction "SDO_5") (pintype "bidirectional"))
      (node (ref "SJ1") (pin "1") (pinfunction "1_1") (pintype "passive"))
      (node (ref "TP4") (pin "TP") (pinfunction "TP_TP") (pintype "input"))
      (node (ref "TP5") (pin "TP") (pinfunction "TP_TP") (pintype "input"))
      (node (ref "U1") (pin "4") (pinfunction "GND_4") (pintype "power_in"))
      (node (ref "U1") (pin "9") (pinfunction "EXP_9") (pintype "passive"))
      (node (ref "U2") (pin "1") (pinfunction "GND_1") (pintype "power_in"))
      (node (ref "U2") (pin "28") (pinfunction "GND_28") (pintype "power_in"))
      (node (ref "U2") (pin "29_1") (pinfunction "GND_29_1") (pintype "power_in"))
      (node (ref "U2") (pin "29_2") (pinfunction "GND_29_2") (pintype "power_in"))
      (node (ref "U2") (pin "29_3") (pinfunction "GND_29_3") (pintype "power_in"))
      (node (ref "U2") (pin "29_4") (pinfunction "GND_29_4") (pintype "power_in"))
      (node (ref "U2") (pin "29_5") (pinfunction "GND_29_5") (pintype "power_in"))
      (node (ref "U2") (pin "29_6") (pinfunction "GND_29_6") (pintype "power_in"))
      (node (ref "U2") (pin "29_7") (pinfunction "GND_29_7") (pintype "power_in"))
      (node (ref "U2") (pin "29_8") (pinfunction "GND_29_8") (pintype "power_in"))
      (node (ref "U2") (pin "29_9") (pinfunction "GND_29_9") (pintype "power_in"))
      (node (ref "U3") (pin "13") (pinfunction "GND_13") (pintype "power_in"))
      (node (ref "U4") (pin "1") (pinfunction "CTG_1") (pintype "power_in"))
      (node (ref "U4") (pin "4") (pinfunction "GND_4") (pintype "power_in"))
      (node (ref "U4") (pin "6") (pinfunction "QSTRT_6") (pintype "input"))
      (node (ref "U4") (pin "9") (pinfunction "EP_9") (pintype "power_in"))
    )
    (net (code "14") (name "GPIO8") (class "Default")
      (node (ref "R1") (pin "1") (pinfunction "1_1") (pintype "passive"))
      (node (ref "U2") (pin "10") (pinfunction "IO8_10") (pintype "bidirectional"))
    )
    (net (code "15") (name "I2C_PW") (class "Default")
      (node (ref "C1") (pin "1") (pinfunction "1_1") (pintype "passive"))
      (node (ref "C2") (pin "1") (pinfunction "1_1") (pintype "passive"))
      (node (ref "R1_PINH") (pin "2") (pinfunction "2_2") (pintype "passive"))
      (node (ref "R2_PINH") (pin "2") (pinfunction "2_2") (pintype "passive"))
      (node (ref "SENSOR2") (pin "1") (pinfunction "CSB_1") (pintype "input"))
      (node (ref "SENSOR2") (pin "6") (pinfunction "VDD_6") (pintype "power_in"))
      (node (ref "SENSOR2") (pin "7") (pinfunction "VDDIO_7") (pintype "power_in"))
      (node (ref "U2") (pin "17") (pinfunction "IO19_17") (pintype "bidirectional"))
    )
    (net (code "16") (name "INT_RTC") (class "Default")
      (node (ref "R1_PINH1") (pin "1") (pinfunction "1_1") (pintype "passive"))
      (node (ref "TP15") (pin "TP") (pinfunction "TP_TP") (pintype "input"))
      (node (ref "U2") (pin "8") (pinfunction "IO0_8") (pintype "bidirectional"))
      (node (ref "U3") (pin "3") (pinfunction "SQW/~{INT}_3") (pintype "output"))
    )
    (net (code "17") (name "IO{slash}BOOT") (class "Default")
      (node (ref "BOOT_BUTTON") (pin "3") (pinfunction "3_3") (pintype "passive"))
      (node (ref "BOOT_BUTTON") (pin "4") (pinfunction "4_4") (pintype "passive"))
      (node (ref "C6") (pin "1") (pinfunction "1_1") (pintype "passive"))
      (node (ref "R_BOOT") (pin "2") (pinfunction "2_2") (pintype "passive"))
      (node (ref "U2") (pin "15") (pinfunction "IO9_15") (pintype "bidirectional"))
    )
    (net (code "18") (name "IO{slash}CHANGE") (class "Default")
      (node (ref "C10") (pin "1") (pinfunction "1_1") (pintype "passive"))
      (node (ref "CHANGE_BUTTON") (pin "3") (pinfunction "3_3") (pintype "passive"))
      (node (ref "CHANGE_BUTTON") (pin "4") (pinfunction "4_4") (pintype "passive"))
      (node (ref "R_CHANGE") (pin "2") (pinfunction "2_2") (pintype "passive"))
      (node (ref "U2") (pin "23") (pinfunction "IO15_23") (pintype "bidirectional"))
    )
    (net (code "19") (name "MISO") (class "Default")
      (node (ref "D12") (pin "2") (pinfunction "2_2") (pintype "passive"))
      (node (ref "J4") (pin "P7") (pinfunction "DAT0_P7") (pintype "bidirectional"))
      (node (ref "R8") (pin "1") (pinfunction "1_1") (pintype "passive"))
      (node (ref "TP6") (pin "TP") (pinfunction "TP_TP") (pintype "input"))
      (node (ref "U1") (pin "2") (pinfunction "DO(IO1)_2") (pintype "bidirectional"))
      (node (ref "U2") (pin "27") (pinfunction "IO2_27") (pintype "bidirectional"))
    )
    (net (code "20") (name "MOSI") (class "Default")
      (node (ref "D11") (pin "2") (pinfunction "2_2") (pintype "passive"))
      (node (ref "J1") (pin "14") (pinfunction "14_14") (pintype "bidirectional"))
      (node (ref "J4") (pin "P3") (pinfunction "CMD_P3") (pintype "bidirectional"))
      (node (ref "R7") (pin "1") (pinfunction "1_1") (pintype "passive"))
      (node (ref "TP7") (pin "TP") (pinfunction "TP_TP") (pintype "input"))
      (node (ref "U1") (pin "5") (pinfunction "DI(IO0)_5") (pintype "bidirectional"))
      (node (ref "U2") (pin "7") (pinfunction "IO7_7") (pintype "bidirectional"))
    )
    (net (code "21") (name "Net-(CHG_LED-PadC)") (class "Default")
      (node (ref "CHG_LED") (pin "C") (pinfunction "C_C") (pintype "passive"))
      (node (ref "R1_BAT") (pin "1") (pinfunction "1_1") (pintype "passive"))
    )
    (net (code "22") (name "Net-(D2-CATHODE)") (class "Default")
      (node (ref "C1_BAT1") (pin "1") (pinfunction "1_1") (pintype "passive"))
      (node (ref "D2") (pin "1") (pinfunction "CATHODE_1") (pintype "bidirectional"))
      (node (ref "IC4") (pin "1") (pinfunction "VIN_1") (pintype "bidirectional"))
      (node (ref "IC4") (pin "3") (pinfunction "CE_3") (pintype "bidirectional"))
      (node (ref "Q1") (pin "2") (pinfunction "S_2") (pintype "bidirectional"))
    )
    (net (code "23") (name "Net-(D3-A)") (class "Default")
      (node (ref "C4") (pin "1") (pinfunction "1_1") (pintype "passive"))
      (node (ref "D3") (pin "2") (pinfunction "A_2") (pintype "bidirectional"))
      (node (ref "D4") (pin "1") (pinfunction "K_1") (pintype "bidirectional"))
    )
    (net (code "24") (name "Net-(D7-CATHODE)") (class "Default")
      (node (ref "D7") (pin "1") (pinfunction "CATHODE_1") (pintype "bidirectional"))
      (node (ref "R_CAPACITOR") (pin "2") (pinfunction "2_2") (pintype "passive"))
    )
    (net (code "25") (name "Net-(EPD_C1-Pad2)") (class "Default")
      (node (ref "EPD_C1") (pin "2") (pinfunction "2_2") (pintype "passive"))
      (node (ref "J1") (pin "4") (pinfunction "4_4") (pintype "bidirectional"))
    )
    (net (code "26") (name "Net-(EPD_C2-Pad2)") (class "Default")
      (node (ref "EPD_C2") (pin "2") (pinfunction "2_2") (pintype "passive"))
      (node (ref "J1") (pin "5") (pinfunction "5_5") (pintype "bidirectional"))
    )
    (net (code "27") (name "Net-(EPD_C6-Pad1)") (class "Default")
      (node (ref "EPD_C6") (pin "1") (pinfunction "1_1") (pintype "passive"))
      (node (ref "J1") (pin "18") (pinfunction "18_18") (pintype "bidirectional"))
    )
    (net (code "28") (name "Net-(EPD_C7-Pad1)") (class "Default")
      (node (ref "EPD_C7") (pin "1") (pinfunction "1_1") (pintype "passive"))
      (node (ref "J1") (pin "19") (pinfunction "19_19") (pintype "bidirectional"))
    )
    (net (code "29") (name "Net-(EPD_C8-Pad1)") (class "Default")
      (node (ref "EPD_C8") (pin "1") (pinfunction "1_1") (pintype "passive"))
      (node (ref "J1") (pin "20") (pinfunction "20_20") (pintype "bidirectional"))
    )
    (net (code "30") (name "Net-(EPD_C10-Pad1)") (class "Default")
      (node (ref "EPD_C10") (pin "1") (pinfunction "1_1") (pintype "passive"))
      (node (ref "J1") (pin "22") (pinfunction "22_22") (pintype "bidirectional"))
    )
    (net (code "31") (name "Net-(EPD_C12-Pad1)") (class "Default")
      (node (ref "EPD_C12") (pin "1") (pinfunction "1_1") (pintype "passive"))
      (node (ref "J1") (pin "24") (pinfunction "24_24") (pintype "bidirectional"))
    )
    (net (code "32") (name "Net-(IC1-CT)") (class "Default")
      (node (ref "C_DELAY") (pin "1") (pinfunction "1_1") (pintype "passive"))
      (node (ref "IC1") (pin "5") (pinfunction "CT_5") (pintype "bidirectional"))
    )
    (net (code "33") (name "Net-(J2-PadA5)") (class "Default")
      (node (ref "J2") (pin "A5") (pinfunction "A5_A5") (pintype "bidirectional"))
      (node (ref "R2-USB1") (pin "2") (pinfunction "2_2") (pintype "passive"))
    )
    (net (code "34") (name "Net-(J2-PadB5)") (class "Default")
      (node (ref "J2") (pin "B5") (pinfunction "B5_B5") (pintype "bidirectional"))
      (node (ref "R2-USB") (pin "1") (pinfunction "1_1") (pintype "passive"))
    )
    (net (code "35") (name "Net-(MCP73831-PROG)") (class "Default")
      (node (ref "MCP73831") (pin "5") (pinfunction "PROG_5") (pintype "input"))
      (node (ref "R2_BAT") (pin "2") (pinfunction "2_2") (pintype "passive"))
    )
    (net (code "36") (name "Net-(MCP73831-STAT)") (class "Default")
      (node (ref "MCP73831") (pin "1") (pinfunction "STAT_1") (pintype "output"))
      (node (ref "R1_BAT") (pin "2") (pinfunction "2_2") (pintype "passive"))
    )
    (net (code "37") (name "PREVGH") (class "Default")
      (node (ref "D5") (pin "2") (pinfunction "A_2") (pintype "bidirectional"))
      (node (ref "EPD_C9") (pin "1") (pinfunction "1_1") (pintype "passive"))
      (node (ref "J1") (pin "21") (pinfunction "21_21") (pintype "bidirectional"))
    )
    (net (code "38") (name "PREVGL") (class "Default")
      (node (ref "D4") (pin "2") (pinfunction "A_2") (pintype "bidirectional"))
      (node (ref "EPD_C11") (pin "1") (pinfunction "1_1") (pintype "passive"))
      (node (ref "J1") (pin "23") (pinfunction "23_23") (pintype "bidirectional"))
    )
    (net (code "39") (name "RESE") (class "Default")
      (node (ref "J1") (pin "3") (pinfunction "3_3") (pintype "bidirectional"))
      (node (ref "Q3") (pin "2") (pinfunction "S_2") (pintype "bidirectional"))
      (node (ref "R3") (pin "2") (pinfunction "2_2") (pintype "passive"))
    )
    (net (code "40") (name "RESE'") (class "Default")
      (node (ref "R2") (pin "2") (pinfunction "2_2") (pintype "passive"))
      (node (ref "R3") (pin "1") (pinfunction "1_1") (pintype "passive"))
      (node (ref "SJ1") (pin "2") (pinfunction "2_2") (pintype "passive"))
    )
    (net (code "41") (name "RESET") (class "Default")
      (node (ref "C5") (pin "1") (pinfunction "1_1") (pintype "passive"))
      (node (ref "IC1") (pin "1") (pinfunction "VOUT_1") (pintype "bidirectional"))
      (node (ref "RESET_BUTTON") (pin "3") (pinfunction "3_3") (pintype "passive"))
      (node (ref "RESET_BUTTON") (pin "4") (pinfunction "4_4") (pintype "passive"))
      (node (ref "R_RESET") (pin "2") (pinfunction "2_2") (pintype "passive"))
      (node (ref "U2") (pin "3") (pinfunction "EN_3") (pintype "input"))
    )
    (net (code "42") (name "RTC_RST") (class "Default")
      (node (ref "U2") (pin "16") (pinfunction "IO18_16") (pintype "bidirectional"))
      (node (ref "U3") (pin "4") (pinfunction "~{RST}_4") (pintype "input"))
    )
    (net (code "43") (name "RX") (class "Default")
      (node (ref "TP2") (pin "TP") (pinfunction "TP_TP") (pintype "input"))
      (node (ref "U2") (pin "24") (pinfunction "RXD0/GPIO17_24") (pintype "bidirectional"))
    )
    (net (code "44") (name "SCK") (class "Default")
      (node (ref "D10") (pin "2") (pinfunction "2_2") (pintype "passive"))
      (node (ref "J1") (pin "13") (pinfunction "13_13") (pintype "bidirectional"))
      (node (ref "J4") (pin "P5") (pinfunction "CLK_P5") (pintype "bidirectional"))
      (node (ref "R6") (pin "1") (pinfunction "1_1") (pintype "passive"))
      (node (ref "TP8") (pin "TP") (pinfunction "TP_TP") (pintype "input"))
      (node (ref "U1") (pin "6") (pinfunction "CLK_6") (pintype "input"))
      (node (ref "U2") (pin "6") (pinfunction "IO6_6") (pintype "bidirectional"))
    )
    (net (code "45") (name "SCL") (class "Default")
      (node (ref "J3") (pin "4") (pinfunction "4_4") (pintype "passive"))
      (node (ref "R2_PINH") (pin "1") (pinfunction "1_1") (pintype "passive"))
      (node (ref "SENSOR2") (pin "3") (pinfunction "SCK_3") (pintype "input"))
      (node (ref "U2") (pin "20") (pinfunction "IO22_20") (pintype "bidirectional"))
      (node (ref "U3") (pin "16") (pinfunction "SCL_16") (pintype "input"))
      (node (ref "U4") (pin "7") (pinfunction "SCL_7") (pintype "input"))
    )
    (net (code "46") (name "SDA") (class "Default")
      (node (ref "J3") (pin "3") (pinfunction "3_3") (pintype "passive"))
      (node (ref "R1_PINH") (pin "1") (pinfunction "1_1") (pintype "passive"))
      (node (ref "SENSOR2") (pin "4") (pinfunction "SDI_4") (pintype "bidirectional"))
      (node (ref "U2") (pin "19") (pinfunction "IO21_19") (pintype "bidirectional"))
      (node (ref "U3") (pin "15") (pinfunction "SDA_15") (pintype "bidirectional"))
      (node (ref "U4") (pin "8") (pinfunction "SDA_8") (pintype "bidirectional"))
    )
    (net (code "47") (name "SRC") (class "Default")
      (node (ref "C4") (pin "2") (pinfunction "2_2") (pintype "passive"))
      (node (ref "D5") (pin "1") (pinfunction "K_1") (pintype "bidirectional"))
      (node (ref "L1") (pin "1") (pinfunction "1_1") (pintype "passive"))
      (node (ref "Q3") (pin "3") (pinfunction "D_3") (pintype "bidirectional"))
    )
    (net (code "48") (name "SS_SD") (class "Default")
      (node (ref "D8") (pin "2") (pinfunction "2_2") (pintype "passive"))
      (node (ref "J4") (pin "P2") (pinfunction "CD/DAT3_P2") (pintype "bidirectional"))
      (node (ref "R10") (pin "1") (pinfunction "1_1") (pintype "passive"))
      (node (ref "U2") (pin "4") (pinfunction "IO4_4") (pintype "bidirectional"))
    )
    (net (code "49") (name "TX") (class "Default")
      (node (ref "TP1") (pin "TP") (pinfunction "TP_TP") (pintype "input"))
      (node (ref "U2") (pin "25") (pinfunction "TXD0/GPIO16_25") (pintype "bidirectional"))
    )
    (net (code "50") (name "USB_D+") (class "Default")
      (node (ref "D1") (pin "4") (pinfunction "I/O2_2_4") (pintype "bidirectional"))
      (node (ref "U2") (pin "14") (pinfunction "IO13_14") (pintype "bidirectional"))
    )
    (net (code "51") (name "USB_D-") (class "Default")
      (node (ref "D1") (pin "6") (pinfunction "I/O1_2_6") (pintype "bidirectional"))
      (node (ref "U2") (pin "13") (pinfunction "IO12_13") (pintype "bidirectional"))
    )
    (net (code "52") (name "VBAT") (class "Default")
      (node (ref "C2_BAT") (pin "1") (pinfunction "1_1") (pintype "passive"))
      (node (ref "MCP73831") (pin "3") (pinfunction "VBAT_3") (pintype "power_in"))
      (node (ref "Q1") (pin "3") (pinfunction "D_3") (pintype "bidirectional"))
      (node (ref "TP3") (pin "TP") (pinfunction "TP_TP") (pintype "input"))
      (node (ref "U4") (pin "2") (pinfunction "CELL_2") (pintype "power_in"))
      (node (ref "U4") (pin "3") (pinfunction "VDD_3") (pintype "power_in"))
    )
    (net (code "53") (name "VBUS") (class "Default")
      (node (ref "C1_BAT") (pin "1") (pinfunction "1_1") (pintype "passive"))
      (node (ref "C4_USB") (pin "1") (pinfunction "1_1") (pintype "passive"))
      (node (ref "C5_USB") (pin "1") (pinfunction "1_1") (pintype "passive"))
      (node (ref "CHG_LED") (pin "A") (pinfunction "A_A") (pintype "passive"))
      (node (ref "D1") (pin "2") (pinfunction "GND_2") (pintype "bidirectional"))
      (node (ref "D2") (pin "2") (pinfunction "ANODE_2") (pintype "bidirectional"))
      (node (ref "MCP73831") (pin "4") (pinfunction "VIN_4") (pintype "power_in"))
      (node (ref "PFMF.050.1") (pin "2") (pinfunction "2_2") (pintype "passive"))
      (node (ref "Q1") (pin "1") (pinfunction "G_1") (pintype "bidirectional"))
      (node (ref "R1_PWRUSB") (pin "1") (pinfunction "1_1") (pintype "passive"))
      (node (ref "TP14") (pin "TP") (pinfunction "TP_TP") (pintype "input"))
    )
    (net (code "54") (name "VRTC") (class "Default")
      (node (ref "C10_SUPERCAP") (pin "2") (pinfunction "2_2") (pintype "passive"))
      (node (ref "C8") (pin "1") (pinfunction "1_1") (pintype "passive"))
      (node (ref "R_CAPACITOR") (pin "1") (pinfunction "1_1") (pintype "passive"))
      (node (ref "U3") (pin "14") (pinfunction "VBAT_14") (pintype "power_in"))
    )
    (net (code "55") (name "VUSB") (class "Default")
      (node (ref "J2") (pin "A4") (pinfunction "A4_A4") (pintype "bidirectional"))
      (node (ref "J2") (pin "A9") (pinfunction "A9_A9") (pintype "bidirectional"))
      (node (ref "J2") (pin "B4") (pinfunction "B4_B4") (pintype "bidirectional"))
      (node (ref "J2") (pin "B9") (pinfunction "B9_B9") (pintype "bidirectional"))
      (node (ref "PFMF.050.1") (pin "1") (pinfunction "1_1") (pintype "passive"))
    )
    (net (code "56") (name "unconnected-(IC1-NC-Pad4)") (class "Default")
      (node (ref "IC1") (pin "4") (pinfunction "NC_4") (pintype "no_connect"))
    )
    (net (code "57") (name "unconnected-(IC4-NC-Pad4)") (class "Default")
      (node (ref "IC4") (pin "4") (pinfunction "NC_4") (pintype "no_connect"))
    )
    (net (code "58") (name "unconnected-(J1-Pad1)") (class "Default")
      (node (ref "J1") (pin "1") (pinfunction "1_1") (pintype "bidirectional"))
    )
    (net (code "59") (name "unconnected-(J1-Pad6)") (class "Default")
      (node (ref "J1") (pin "6") (pinfunction "6_6") (pintype "bidirectional"))
    )
    (net (code "60") (name "unconnected-(J1-Pad7)") (class "Default")
      (node (ref "J1") (pin "7") (pinfunction "7_7") (pintype "bidirectional"))
    )
    (net (code "61") (name "unconnected-(J2-PadA8)") (class "Default")
      (node (ref "J2") (pin "A8") (pinfunction "A8_A8") (pintype "bidirectional"))
    )
    (net (code "62") (name "unconnected-(J2-PadB8)") (class "Default")
      (node (ref "J2") (pin "B8") (pinfunction "B8_B8") (pintype "bidirectional"))
    )
    (net (code "63") (name "unconnected-(J4-DAT1-PadP8)") (class "Default")
      (node (ref "J4") (pin "P8") (pinfunction "DAT1_P8") (pintype "bidirectional"))
    )
    (net (code "64") (name "unconnected-(J4-DAT2-PadP1)") (class "Default")
      (node (ref "J4") (pin "P1") (pinfunction "DAT2_P1") (pintype "bidirectional"))
    )
    (net (code "65") (name "unconnected-(J4-DETECTION_1-PadS1)") (class "Default")
      (node (ref "J4") (pin "S1") (pinfunction "DETECTION_1_S1") (pintype "bidirectional"))
    )
    (net (code "66") (name "unconnected-(J4-DETECTION_2-PadS2)") (class "Default")
      (node (ref "J4") (pin "S2") (pinfunction "DETECTION_2_S2") (pintype "bidirectional"))
    )
    (net (code "67") (name "unconnected-(U2-NC-Pad22)") (class "Default")
      (node (ref "U2") (pin "22") (pinfunction "NC_22") (pintype "no_connect"))
    )
    (net (code "68") (name "unconnected-(U4-~{ALERT}-Pad5)") (class "Default")
      (node (ref "U4") (pin "5") (pinfunction "~{ALERT}_5") (pintype "output"))
    )
  )
)
